# MCU.net
KiCad netlist of a schematic drawn in Altium Designer
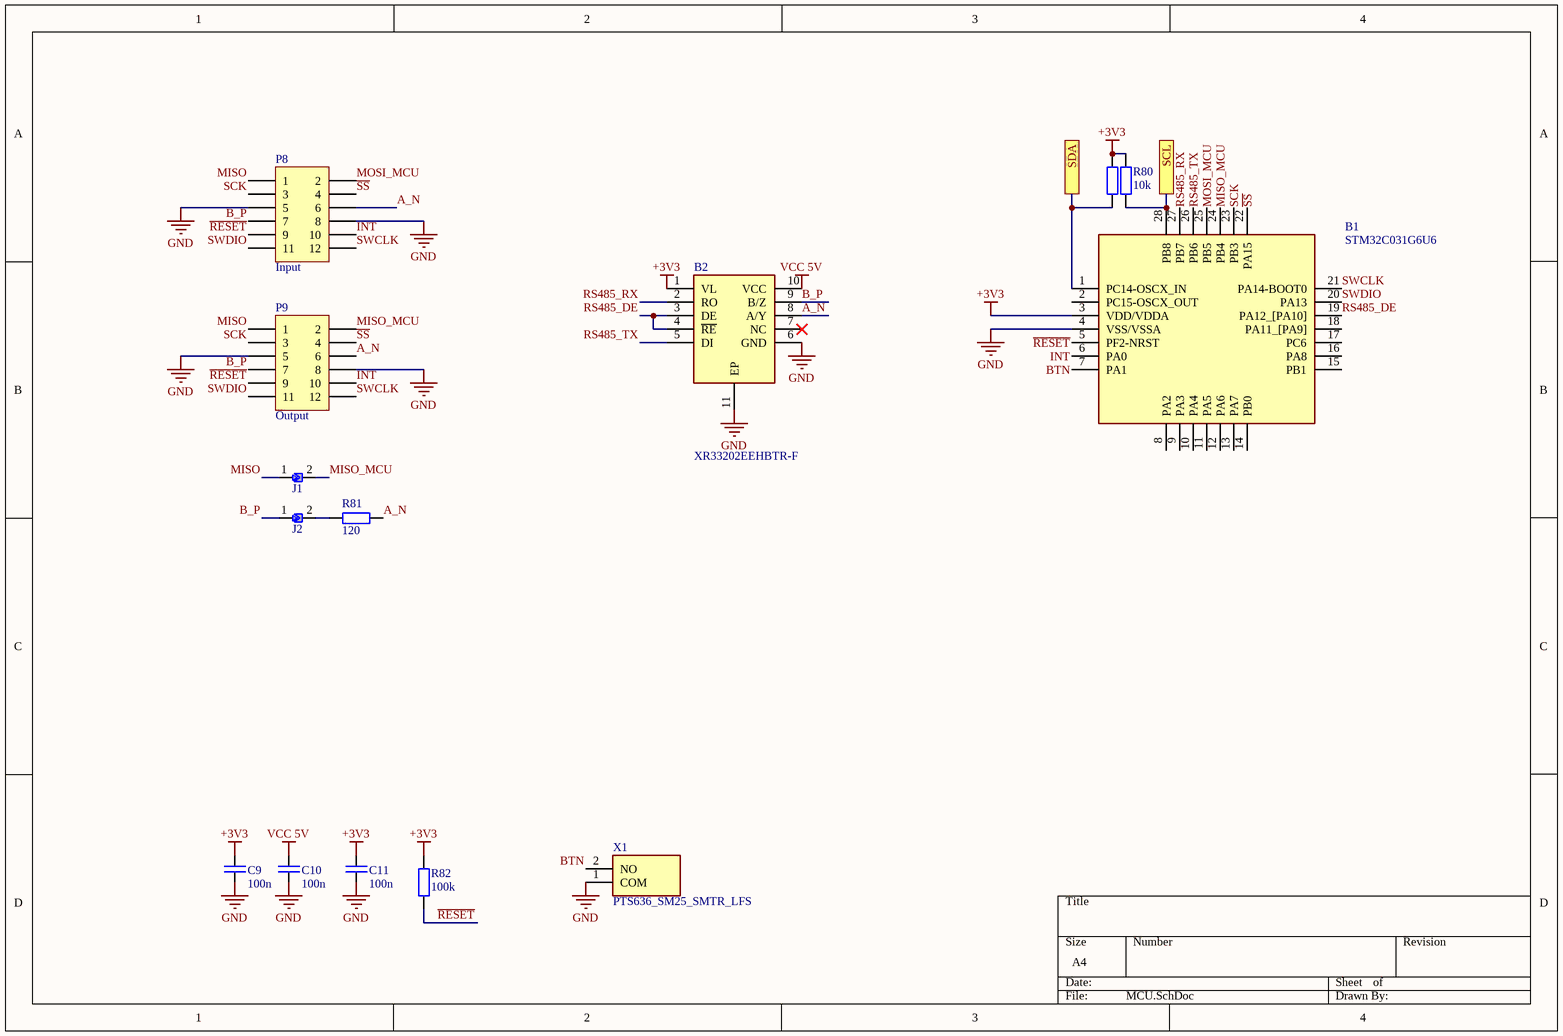
[diagram p0: MCU.SchDoc]

(export (version "E")
  (design (tool "Eeschema 10.0.6"))
  (components
    (comp (ref "B1")
      (value "STM32C031G6U6")
      (footprint "QFN50P400X400X60-28N-D")
      (fields (field (name "MOUSER PART NUMBER") "511-STM32C031G6U6"))
      (libsource (lib "components_library") (part "STM32C031G6U6"))
    )
    (comp (ref "B2")
      (value "XR33202EEHBTR-F")
      (footprint "SON50P300X300X80-11N-D")
      (description "RS-422/RS-485 Interface IC Wide Supply Trans with I/O Interface")
      (fields (field (name "MOUSER PART NUMBER") "701-XR33202EEHBTR-F"))
      (libsource (lib "components_library") (part "XR33202EEHBTR-F"))
    )
    (comp (ref "C9")
      (value "100n")
      (footprint "R1005_0402i_L")
      (description "Capacitor")
      (libsource (lib "General") (part "C"))
    )
    (comp (ref "C10")
      (value "100n")
      (footprint "R1005_0402i_L")
      (description "Capacitor")
      (libsource (lib "General") (part "C"))
    )
    (comp (ref "C11")
      (value "100n")
      (footprint "R1005_0402i_L")
      (description "Capacitor")
      (libsource (lib "General") (part "C"))
    )
    (comp (ref "J1")
      (value "solder_jumper")
      (footprint "solder_jumper_triangle")
      (libsource (lib "components_library") (part "solder_jumper"))
    )
    (comp (ref "J2")
      (value "solder_jumper")
      (footprint "solder_jumper_triangle")
      (libsource (lib "components_library") (part "solder_jumper"))
    )
    (comp (ref "P8")
      (value "Input")
      (footprint "1.27mm SMD conn")
      (description "Header, 6-Pin, Dual row")
      (fields (field (name "PUBLISHER") "Altium Limited"))
      (libsource (lib "Miscellaneous Connectors") (part "Header 6X2"))
    )
    (comp (ref "P9")
      (value "Output")
      (footprint "1.27mm SMD conn")
      (description "Header, 6-Pin, Dual row")
      (fields (field (name "PUBLISHER") "Altium Limited"))
      (libsource (lib "Miscellaneous Connectors") (part "Header 6X2"))
    )
    (comp (ref "R79")
      (value "10k")
      (footprint "R1005_0402i_L")
      (description "R")
      (libsource (lib "General") (part "R"))
    )
    (comp (ref "R80")
      (value "10k")
      (footprint "R1005_0402i_L")
      (description "R")
      (libsource (lib "General") (part "R"))
    )
    (comp (ref "R81")
      (value "120")
      (footprint "R1005_0402i_L")
      (description "R")
      (libsource (lib "General") (part "R"))
    )
    (comp (ref "R82")
      (value "100k")
      (footprint "R1005_0402i_L")
      (description "R")
      (libsource (lib "General") (part "R"))
    )
    (comp (ref "X1")
      (value "PTS636_SM25_SMTR_LFS")
      (footprint "PTS636SM25SMTRLFS")
      (description "Tactile Switches Tact 50mA 12VDC, 6.0x3.5, 2.5mm H, 180gf, G leads, No ground pin, White Actuator")
      (fields
        (field (name "MOUSER PART NUMBER") "611-PTS636SM25SMTRLF")
        (field (name "MANUFACTURER_PART_NUMBER") "PTS636 SM25 SMTR LFS")
      )
      (libsource (lib "components_library") (part "PTS636_SM25_SMTR_LFS"))
    )
  )
  (nets
    (net (code "1") (name "+3V3") (class "Default")
      (node (ref "B1") (pin "3") (pinfunction "VDD/VDDA_3") (pintype "passive"))
      (node (ref "B2") (pin "1") (pinfunction "VL_1") (pintype "passive"))
      (node (ref "C11") (pin "1") (pinfunction "1_1") (pintype "passive"))
      (node (ref "C9") (pin "1") (pinfunction "1_1") (pintype "passive"))
      (node (ref "R79") (pin "1") (pintype "passive"))
      (node (ref "R80") (pin "1") (pintype "passive"))
      (node (ref "R82") (pin "1") (pintype "passive"))
    )
    (net (code "2") (name "/A_N") (class "Default")
      (node (ref "B2") (pin "8") (pinfunction "A/Y_8") (pintype "passive"))
      (node (ref "P8") (pin "6") (pinfunction "6_6") (pintype "passive"))
      (node (ref "P9") (pin "6") (pinfunction "6_6") (pintype "passive"))
      (node (ref "R81") (pin "2") (pintype "passive"))
    )
    (net (code "3") (name "/BTN") (class "Default")
      (node (ref "B1") (pin "7") (pinfunction "PA1_7") (pintype "passive"))
      (node (ref "X1") (pin "2") (pinfunction "NO_2") (pintype "passive"))
    )
    (net (code "4") (name "/B_P") (class "Default")
      (node (ref "B2") (pin "9") (pinfunction "B/Z_9") (pintype "passive"))
      (node (ref "J2") (pin "1") (pintype "passive"))
      (node (ref "P8") (pin "7") (pinfunction "7_7") (pintype "passive"))
      (node (ref "P9") (pin "7") (pinfunction "7_7") (pintype "passive"))
    )
    (net (code "5") (name "/INT") (class "Default")
      (node (ref "B1") (pin "6") (pinfunction "PA0_6") (pintype "passive"))
      (node (ref "P8") (pin "10") (pinfunction "10_10") (pintype "passive"))
      (node (ref "P9") (pin "10") (pinfunction "10_10") (pintype "passive"))
    )
    (net (code "6") (name "/MISO") (class "Default")
      (node (ref "J1") (pin "1") (pintype "passive"))
      (node (ref "P8") (pin "1") (pinfunction "1_1") (pintype "passive"))
      (node (ref "P9") (pin "1") (pinfunction "1_1") (pintype "passive"))
    )
    (net (code "7") (name "/MISO_MCU") (class "Default")
      (node (ref "B1") (pin "24") (pinfunction "PB4_24") (pintype "passive"))
      (node (ref "J1") (pin "2") (pintype "passive"))
      (node (ref "P9") (pin "2") (pinfunction "2_2") (pintype "passive"))
    )
    (net (code "8") (name "/MOSI_MCU") (class "Default")
      (node (ref "B1") (pin "25") (pinfunction "PB5_25") (pintype "passive"))
      (node (ref "P8") (pin "2") (pinfunction "2_2") (pintype "passive"))
    )
    (net (code "9") (name "/RS485_DE") (class "Default")
      (node (ref "B1") (pin "19") (pinfunction "PA12_[PA10]_19") (pintype "passive"))
      (node (ref "B2") (pin "3") (pinfunction "DE_3") (pintype "passive"))
      (node (ref "B2") (pin "4") (pinfunction "~{RE}_4") (pintype "passive"))
    )
    (net (code "10") (name "/RS485_RX") (class "Default")
      (node (ref "B1") (pin "27") (pinfunction "PB7_27") (pintype "passive"))
      (node (ref "B2") (pin "2") (pinfunction "RO_2") (pintype "passive"))
    )
    (net (code "11") (name "/RS485_TX") (class "Default")
      (node (ref "B1") (pin "26") (pinfunction "PB6_26") (pintype "passive"))
      (node (ref "B2") (pin "5") (pinfunction "DI_5") (pintype "passive"))
    )
    (net (code "12") (name "/SCK") (class "Default")
      (node (ref "B1") (pin "23") (pinfunction "PB3_23") (pintype "passive"))
      (node (ref "P8") (pin "3") (pinfunction "3_3") (pintype "passive"))
      (node (ref "P9") (pin "3") (pinfunction "3_3") (pintype "passive"))
    )
    (net (code "13") (name "/SCL") (class "Default")
      (node (ref "B1") (pin "28") (pinfunction "PB8_28") (pintype "passive"))
      (node (ref "R80") (pin "2") (pintype "passive"))
    )
    (net (code "14") (name "/SDA") (class "Default")
      (node (ref "B1") (pin "1") (pinfunction "PC14-OSCX_IN_1") (pintype "passive"))
      (node (ref "R79") (pin "2") (pintype "passive"))
    )
    (net (code "15") (name "/SWCLK") (class "Default")
      (node (ref "B1") (pin "21") (pinfunction "PA14-BOOT0_21") (pintype "passive"))
      (node (ref "P8") (pin "12") (pinfunction "12_12") (pintype "passive"))
      (node (ref "P9") (pin "12") (pinfunction "12_12") (pintype "passive"))
    )
    (net (code "16") (name "/SWDIO") (class "Default")
      (node (ref "B1") (pin "20") (pinfunction "PA13_20") (pintype "passive"))
      (node (ref "P8") (pin "11") (pinfunction "11_11") (pintype "passive"))
      (node (ref "P9") (pin "11") (pinfunction "11_11") (pintype "passive"))
    )
    (net (code "17") (name "/~{RESET}") (class "Default")
      (node (ref "B1") (pin "5") (pinfunction "PF2-NRST_5") (pintype "passive"))
      (node (ref "P8") (pin "9") (pinfunction "9_9") (pintype "passive"))
      (node (ref "P9") (pin "9") (pinfunction "9_9") (pintype "passive"))
      (node (ref "R82") (pin "2") (pintype "passive"))
    )
    (net (code "18") (name "/~{SS}") (class "Default")
      (node (ref "B1") (pin "22") (pinfunction "PA15_22") (pintype "passive"))
      (node (ref "P8") (pin "4") (pinfunction "4_4") (pintype "passive"))
      (node (ref "P9") (pin "4") (pinfunction "4_4") (pintype "passive"))
    )
    (net (code "19") (name "GND") (class "Default")
      (node (ref "B1") (pin "4") (pinfunction "VSS/VSSA_4") (pintype "passive"))
      (node (ref "B2") (pin "11") (pinfunction "EP_11") (pintype "passive"))
      (node (ref "B2") (pin "6") (pinfunction "GND_6") (pintype "passive"))
      (node (ref "C10") (pin "2") (pinfunction "2_2") (pintype "passive"))
      (node (ref "C11") (pin "2") (pinfunction "2_2") (pintype "passive"))
      (node (ref "C9") (pin "2") (pinfunction "2_2") (pintype "passive"))
      (node (ref "P8") (pin "5") (pinfunction "5_5") (pintype "passive"))
      (node (ref "P8") (pin "8") (pinfunction "8_8") (pintype "passive"))
      (node (ref "P9") (pin "5") (pinfunction "5_5") (pintype "passive"))
      (node (ref "P9") (pin "8") (pinfunction "8_8") (pintype "passive"))
      (node (ref "X1") (pin "1") (pinfunction "COM_1") (pintype "passive"))
    )
    (net (code "20") (name "Net-(J2-Pad2)") (class "Default")
      (node (ref "J2") (pin "2") (pintype "passive"))
      (node (ref "R81") (pin "1") (pintype "passive"))
    )
    (net (code "21") (name "VCC 5V") (class "Default")
      (node (ref "B2") (pin "10") (pinfunction "VCC_10") (pintype "passive"))
      (node (ref "C10") (pin "1") (pinfunction "1_1") (pintype "passive"))
    )
    (net (code "22") (name "unconnected-(B1-PA2-Pad8)") (class "Default")
      (node (ref "B1") (pin "8") (pinfunction "PA2_8") (pintype "passive"))
    )
    (net (code "23") (name "unconnected-(B1-PA3-Pad9)") (class "Default")
      (node (ref "B1") (pin "9") (pinfunction "PA3_9") (pintype "passive"))
    )
    (net (code "24") (name "unconnected-(B1-PA4-Pad10)") (class "Default")
      (node (ref "B1") (pin "10") (pinfunction "PA4_10") (pintype "passive"))
    )
    (net (code "25") (name "unconnected-(B1-PA5-Pad11)") (class "Default")
      (node (ref "B1") (pin "11") (pinfunction "PA5_11") (pintype "passive"))
    )
    (net (code "26") (name "unconnected-(B1-PA6-Pad12)") (class "Default")
      (node (ref "B1") (pin "12") (pinfunction "PA6_12") (pintype "passive"))
    )
    (net (code "27") (name "unconnected-(B1-PA7-Pad13)") (class "Default")
      (node (ref "B1") (pin "13") (pinfunction "PA7_13") (pintype "passive"))
    )
    (net (code "28") (name "unconnected-(B1-PA8-Pad16)") (class "Default")
      (node (ref "B1") (pin "16") (pinfunction "PA8_16") (pintype "passive"))
    )
    (net (code "29") (name "unconnected-(B1-PA11_[PA9]-Pad18)") (class "Default")
      (node (ref "B1") (pin "18") (pinfunction "PA11_[PA9]_18") (pintype "passive"))
    )
    (net (code "30") (name "unconnected-(B1-PB0-Pad14)") (class "Default")
      (node (ref "B1") (pin "14") (pinfunction "PB0_14") (pintype "passive"))
    )
    (net (code "31") (name "unconnected-(B1-PB1-Pad15)") (class "Default")
      (node (ref "B1") (pin "15") (pinfunction "PB1_15") (pintype "passive"))
    )
    (net (code "32") (name "unconnected-(B1-PC6-Pad17)") (class "Default")
      (node (ref "B1") (pin "17") (pinfunction "PC6_17") (pintype "passive"))
    )
    (net (code "33") (name "unconnected-(B1-PC15-OSCX_OUT-Pad2)") (class "Default")
      (node (ref "B1") (pin "2") (pinfunction "PC15-OSCX_OUT_2") (pintype "passive"))
    )
    (net (code "34") (name "unconnected-(B2-NC-Pad7)") (class "Default")
      (node (ref "B2") (pin "7") (pinfunction "NC_7") (pintype "passive+no_connect"))
    )
  )
)
